# FMtransmitter.net
KiCad netlist of a schematic drawn in EAGLE
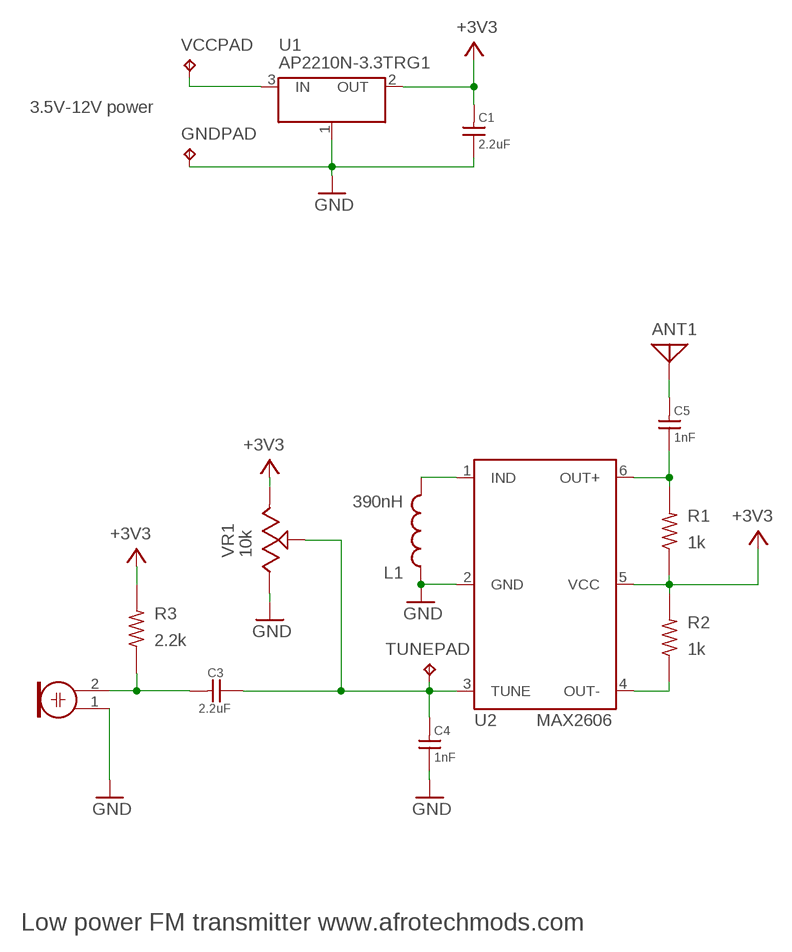
[diagram p0: schematic, sheet 1]

(export (version "E")
  (design (tool "Eeschema 10.0.6"))
  (components
    (comp (ref "ANT1")
      (value "ANTENNA")
      (footprint "eagle-import:PAD-01")
      (libsource (lib "eagle-import") (part "ANTENNA"))
    )
    (comp (ref "C1")
      (value "2.2uF")
      (footprint "eagle-import:0805")
      (libsource (lib "eagle-import") (part "CAPACITOR-0805"))
    )
    (comp (ref "C3")
      (value "2.2uF")
      (footprint "eagle-import:0805")
      (libsource (lib "eagle-import") (part "CAPACITOR-0805"))
    )
    (comp (ref "C4")
      (value "1nF")
      (footprint "eagle-import:0805")
      (libsource (lib "eagle-import") (part "CAPACITOR-0805"))
    )
    (comp (ref "C5")
      (value "1nF")
      (footprint "eagle-import:0805")
      (libsource (lib "eagle-import") (part "CAPACITOR-0805"))
    )
    (comp (ref "GNDPAD")
      (value "TPPAD1-13")
      (footprint "eagle-import:P1-13")
      (libsource (lib "eagle-import") (part "TPPAD1-13"))
    )
    (comp (ref "L1")
      (value "390nH")
      (footprint "eagle-import:0805")
      (libsource (lib "eagle-import") (part "INDUCTOR-0805"))
    )
    (comp (ref "MK1")
      (value "ELECTRET_MICROPHON-WM-64PC/64PK")
      (footprint "eagle-import:WM-64PC_64PK")
      (libsource (lib "eagle-import") (part "ELECTRET_MICROPHON-WM-64PC/64PK"))
    )
    (comp (ref "R1")
      (value "1k")
      (footprint "eagle-import:0805")
      (libsource (lib "eagle-import") (part "RESISTOR-0805"))
    )
    (comp (ref "R2")
      (value "1k")
      (footprint "eagle-import:0805")
      (libsource (lib "eagle-import") (part "RESISTOR-0805"))
    )
    (comp (ref "R3")
      (value "2.2k")
      (footprint "eagle-import:0805")
      (libsource (lib "eagle-import") (part "RESISTOR-0805"))
    )
    (comp (ref "TUNEPAD")
      (value "TPPAD1-13")
      (footprint "eagle-import:P1-13")
      (libsource (lib "eagle-import") (part "TPPAD1-13"))
    )
    (comp (ref "U1")
      (value "AP2210N-3.3TRG1")
      (footprint "eagle-import:SOT-23")
      (libsource (lib "eagle-import") (part "AP2210N-3.3TRG1"))
    )
    (comp (ref "U2")
      (value "MAX2606")
      (footprint "eagle-import:SOT23-6")
      (libsource (lib "eagle-import") (part "MAX2606"))
    )
    (comp (ref "VCCPAD")
      (value "TPPAD1-13")
      (footprint "eagle-import:P1-13")
      (libsource (lib "eagle-import") (part "TPPAD1-13"))
    )
    (comp (ref "VR1")
      (value "10k")
      (footprint "eagle-import:SMDPOT")
      (libsource (lib "eagle-import") (part "TRIMPOT"))
    )
  )
  (nets
    (net (code "1") (name "+3V3") (class "Default")
      (node (ref "C1") (pin "P$2") (pinfunction "2_P$2") (pintype "passive"))
      (node (ref "R1") (pin "P$2") (pinfunction "2_P$2") (pintype "passive"))
      (node (ref "R2") (pin "P$1") (pinfunction "1_P$1") (pintype "passive"))
      (node (ref "R3") (pin "P$1") (pinfunction "1_P$1") (pintype "passive"))
      (node (ref "U1") (pin "2") (pinfunction "OUT_2") (pintype "passive"))
      (node (ref "U2") (pin "5") (pinfunction "VCC_5") (pintype "bidirectional"))
      (node (ref "VR1") (pin "3") (pinfunction "E_3") (pintype "passive"))
    )
    (net (code "2") (name "GND") (class "Default")
      (node (ref "C1") (pin "P$1") (pinfunction "1_P$1") (pintype "passive"))
      (node (ref "C4") (pin "P$1") (pinfunction "1_P$1") (pintype "passive"))
      (node (ref "GNDPAD") (pin "TP") (pinfunction "TP_TP") (pintype "input"))
      (node (ref "L1") (pin "P$1") (pinfunction "1_P$1") (pintype "passive"))
      (node (ref "MK1") (pin "1") (pinfunction "1_1") (pintype "passive"))
      (node (ref "U1") (pin "1") (pinfunction "GND_1") (pintype "passive"))
      (node (ref "U2") (pin "2") (pinfunction "GND_2") (pintype "bidirectional"))
      (node (ref "VR1") (pin "1") (pinfunction "A_1") (pintype "passive"))
    )
    (net (code "3") (name "Net-(C3-1)") (class "Default")
      (node (ref "C3") (pin "P$1") (pinfunction "1_P$1") (pintype "passive"))
      (node (ref "C4") (pin "P$2") (pinfunction "2_P$2") (pintype "passive"))
      (node (ref "TUNEPAD") (pin "TP") (pinfunction "TP_TP") (pintype "input"))
      (node (ref "U2") (pin "3") (pinfunction "TUNE_3") (pintype "bidirectional"))
      (node (ref "VR1") (pin "2") (pinfunction "WIPER_2") (pintype "passive"))
    )
    (net (code "4") (name "Net-(C3-2)") (class "Default")
      (node (ref "C3") (pin "P$2") (pinfunction "2_P$2") (pintype "passive"))
      (node (ref "MK1") (pin "2") (pinfunction "2_2") (pintype "passive"))
      (node (ref "R3") (pin "P$2") (pinfunction "2_P$2") (pintype "passive"))
    )
    (net (code "5") (name "Net-(C5-1)") (class "Default")
      (node (ref "C5") (pin "P$1") (pinfunction "1_P$1") (pintype "passive"))
      (node (ref "R1") (pin "P$1") (pinfunction "1_P$1") (pintype "passive"))
      (node (ref "U2") (pin "6") (pinfunction "OUT+_6") (pintype "bidirectional"))
    )
    (net (code "6") (name "Net-(C5-2)") (class "Default")
      (node (ref "ANT1") (pin "1") (pinfunction "1_1") (pintype "output"))
      (node (ref "C5") (pin "P$2") (pinfunction "2_P$2") (pintype "passive"))
    )
    (net (code "7") (name "Net-(L1-2)") (class "Default")
      (node (ref "L1") (pin "P$2") (pinfunction "2_P$2") (pintype "passive"))
      (node (ref "U2") (pin "1") (pinfunction "IND_1") (pintype "bidirectional"))
    )
    (net (code "8") (name "Net-(R2-2)") (class "Default")
      (node (ref "R2") (pin "P$2") (pinfunction "2_P$2") (pintype "passive"))
      (node (ref "U2") (pin "4") (pinfunction "OUT-_4") (pintype "bidirectional"))
    )
    (net (code "9") (name "Net-(U1-IN)") (class "Default")
      (node (ref "U1") (pin "3") (pinfunction "IN_3") (pintype "passive"))
      (node (ref "VCCPAD") (pin "TP") (pinfunction "TP_TP") (pintype "input"))
    )
  )
)
